# lcd_panel_adapter.net
KiCad netlist of a schematic drawn in EAGLE
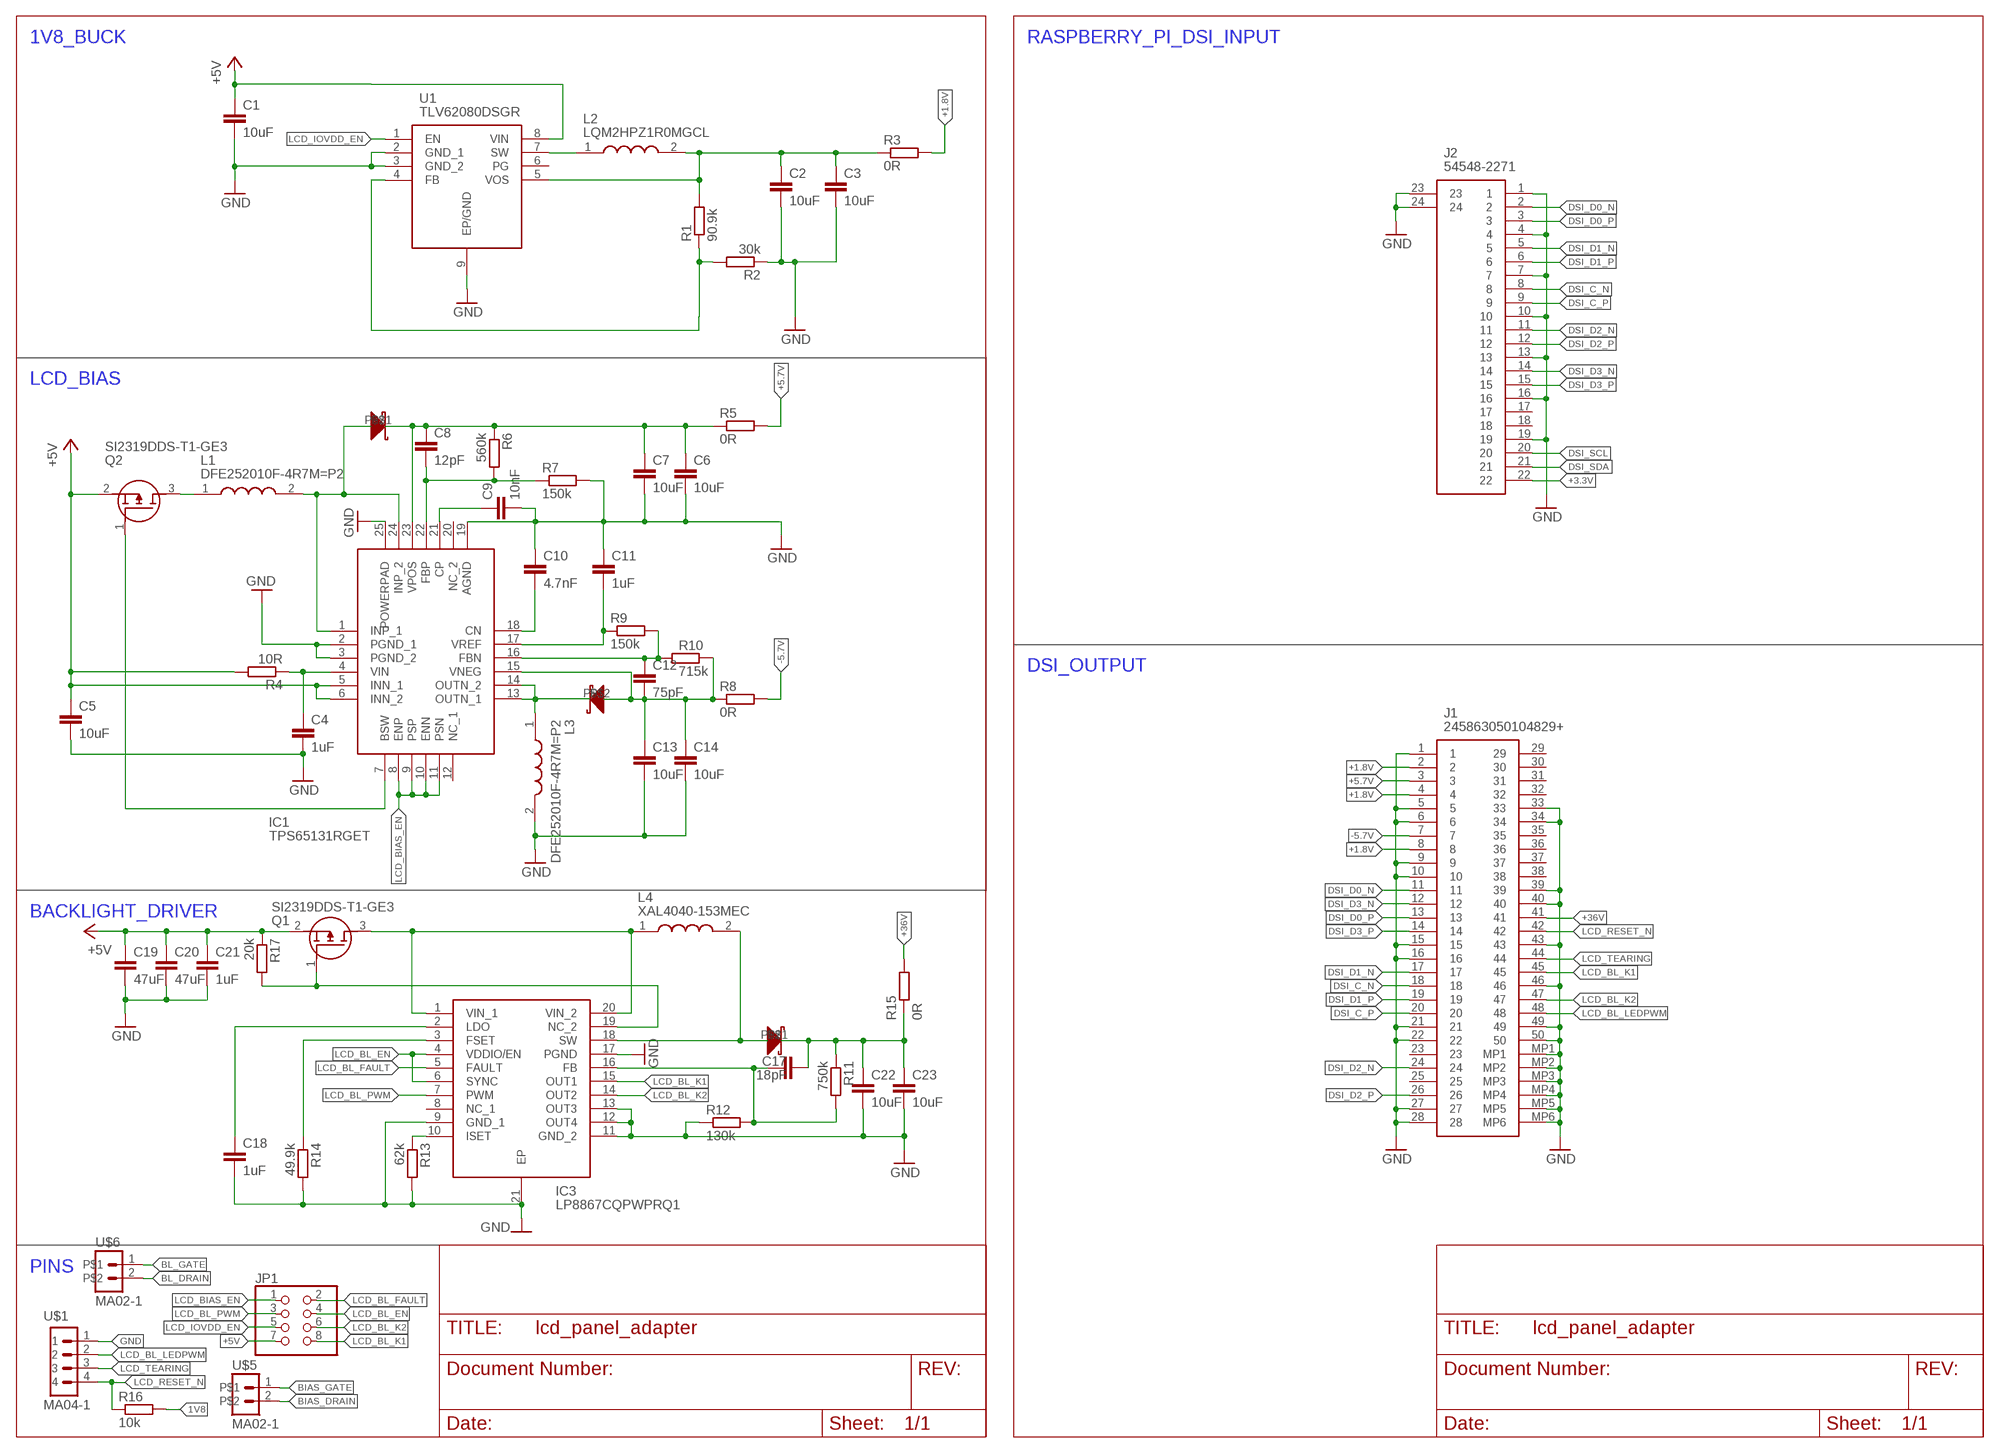
[diagram p0: schematic, sheet 1]

(export (version "E")
  (design (tool "Eeschema 10.0.6"))
  (components
    (comp (ref "C1")
      (value "10uF")
      (footprint "eagle-import:C0603")
      (libsource (lib "eagle-import") (part "C-EUC0603"))
    )
    (comp (ref "C2")
      (value "10uF")
      (footprint "eagle-import:C0603")
      (libsource (lib "eagle-import") (part "C-EUC0603"))
    )
    (comp (ref "C3")
      (value "10uF")
      (footprint "eagle-import:C0603")
      (libsource (lib "eagle-import") (part "C-EUC0603"))
    )
    (comp (ref "C4")
      (value "1uF")
      (footprint "eagle-import:C0603")
      (libsource (lib "eagle-import") (part "C-EUC0603"))
    )
    (comp (ref "C5")
      (value "10uF")
      (footprint "eagle-import:C0603")
      (libsource (lib "eagle-import") (part "C-EUC0603"))
    )
    (comp (ref "C6")
      (value "10uF")
      (footprint "eagle-import:C0603")
      (libsource (lib "eagle-import") (part "C-EUC0603"))
    )
    (comp (ref "C7")
      (value "10uF")
      (footprint "eagle-import:C0603")
      (libsource (lib "eagle-import") (part "C-EUC0603"))
    )
    (comp (ref "C8")
      (value "12pF")
      (footprint "eagle-import:C0603")
      (libsource (lib "eagle-import") (part "C-EUC0603"))
    )
    (comp (ref "C9")
      (value "10nF")
      (footprint "eagle-import:C0603")
      (libsource (lib "eagle-import") (part "C-EUC0603"))
    )
    (comp (ref "C10")
      (value "4.7nF")
      (footprint "eagle-import:C0603")
      (libsource (lib "eagle-import") (part "C-EUC0603"))
    )
    (comp (ref "C11")
      (value "1uF")
      (footprint "eagle-import:C0603")
      (libsource (lib "eagle-import") (part "C-EUC0603"))
    )
    (comp (ref "C12")
      (value "75pF")
      (footprint "eagle-import:C0603")
      (libsource (lib "eagle-import") (part "C-EUC0603"))
    )
    (comp (ref "C13")
      (value "10uF")
      (footprint "eagle-import:C0603")
      (libsource (lib "eagle-import") (part "C-EUC0603"))
    )
    (comp (ref "C14")
      (value "10uF")
      (footprint "eagle-import:C0603")
      (libsource (lib "eagle-import") (part "C-EUC0603"))
    )
    (comp (ref "C17")
      (value "18pF")
      (footprint "eagle-import:C0603")
      (libsource (lib "eagle-import") (part "C-EUC0603"))
    )
    (comp (ref "C18")
      (value "1uF")
      (footprint "eagle-import:C0603")
      (libsource (lib "eagle-import") (part "C-EUC0603"))
    )
    (comp (ref "C19")
      (value "47uF")
      (footprint "eagle-import:C0603")
      (libsource (lib "eagle-import") (part "C-EUC0603"))
    )
    (comp (ref "C20")
      (value "47uF")
      (footprint "eagle-import:C0603")
      (libsource (lib "eagle-import") (part "C-EUC0603"))
    )
    (comp (ref "C21")
      (value "1uF")
      (footprint "eagle-import:C0603")
      (libsource (lib "eagle-import") (part "C-EUC0603"))
    )
    (comp (ref "C22")
      (value "10uF")
      (footprint "eagle-import:C1206")
      (libsource (lib "eagle-import") (part "C-EUC1206"))
    )
    (comp (ref "C23")
      (value "10uF")
      (footprint "eagle-import:C1206")
      (libsource (lib "eagle-import") (part "C-EUC1206"))
    )
    (comp (ref "IC1")
      (value "TPS65131RGET")
      (footprint "eagle-import:QFN50P400X400X100-25N")
      (fields (field (name "MOUSER_PART_NUMBER") "595-TPS65131RGET"))
      (libsource (lib "eagle-import") (part "TPS65131RGET"))
    )
    (comp (ref "IC3")
      (value "LP8867CQPWPRQ1")
      (footprint "eagle-import:SOP65P640X120-21N")
      (fields
        (field (name "MANUFACTURER_PART_NUMBER") "TPS61194PWPR")
        (field (name "MOUSER_PART_NUMBER") "595-TPS61194PWPR")
      )
      (libsource (lib "eagle-import") (part "TPS61194PWPR"))
    )
    (comp (ref "J1")
      (value "245863050104829+")
      (footprint "eagle-import:245863050104829")
      (fields (field (name "MOUSER_PART_NUMBER") "346-245863050104829+"))
      (libsource (lib "eagle-import") (part "245863050104829+"))
    )
    (comp (ref "J2")
      (value "54548-2271")
      (footprint "eagle-import:545482271")
      (fields (field (name "MOUSER_PART_NUMBER") "538-54548-2271"))
      (libsource (lib "eagle-import") (part "54548-2271"))
    )
    (comp (ref "JP1")
      (value "PINHD-2X4")
      (footprint "eagle-import:2X04")
      (libsource (lib "eagle-import") (part "PINHD-2X4"))
    )
    (comp (ref "L1")
      (value "DFE252010F-4R7M=P2")
      (footprint "eagle-import:1269ASH100NP2")
      (fields (field (name "MOUSER_PART_NUMBER") "81-DFE252010F-4R7MP2"))
      (libsource (lib "eagle-import") (part "DFE252010F-4R7M=P2"))
    )
    (comp (ref "L2")
      (value "LQM2HPZ1R0MGCL")
      (footprint "eagle-import:LQM2HPN1R0MG0L")
      (libsource (lib "eagle-import") (part "LQM2HPZ1R0MGCL"))
    )
    (comp (ref "L3")
      (value "DFE252010F-4R7M=P2")
      (footprint "eagle-import:1269ASH100NP2")
      (fields (field (name "MOUSER_PART_NUMBER") "81-DFE252010F-4R7MP2"))
      (libsource (lib "eagle-import") (part "DFE252010F-4R7M=P2"))
    )
    (comp (ref "L4")
      (value "XAL4040-153MEC")
      (footprint "eagle-import:XAL4040153MEC")
      (fields (field (name "MOUSER_PART_NUMBER") "994-XAL4040-153MEC"))
      (libsource (lib "eagle-import") (part "XAL4040-153MEC"))
    )
    (comp (ref "Q1")
      (value "SI2319DDS-T1-GE3")
      (footprint "eagle-import:SOT96P240X120-3N")
      (fields (field (name "MOUSER_PART_NUMBER") "78-SI2319DDS-T1-GE3"))
      (libsource (lib "eagle-import") (part "SI2319DDS-T1-GE3"))
    )
    (comp (ref "Q2")
      (value "SI2319DDS-T1-GE3")
      (footprint "eagle-import:SOT96P240X120-3N")
      (fields (field (name "MOUSER_PART_NUMBER") "78-SI2319DDS-T1-GE3"))
      (libsource (lib "eagle-import") (part "SI2319DDS-T1-GE3"))
    )
    (comp (ref "R1")
      (value "90.9k")
      (footprint "eagle-import:R0603")
      (libsource (lib "eagle-import") (part "R-EU_R0603"))
    )
    (comp (ref "R2")
      (value "30k")
      (footprint "eagle-import:R0603")
      (libsource (lib "eagle-import") (part "R-EU_R0603"))
    )
    (comp (ref "R3")
      (value "0R")
      (footprint "eagle-import:R0603")
      (libsource (lib "eagle-import") (part "R-EU_R0603"))
    )
    (comp (ref "R4")
      (value "10R")
      (footprint "eagle-import:R0603")
      (libsource (lib "eagle-import") (part "R-EU_R0603"))
    )
    (comp (ref "R5")
      (value "0R")
      (footprint "eagle-import:R0603")
      (libsource (lib "eagle-import") (part "R-EU_R0603"))
    )
    (comp (ref "R6")
      (value "560k")
      (footprint "eagle-import:R0603")
      (libsource (lib "eagle-import") (part "R-EU_R0603"))
    )
    (comp (ref "R7")
      (value "150k")
      (footprint "eagle-import:R0603")
      (libsource (lib "eagle-import") (part "R-EU_R0603"))
    )
    (comp (ref "R8")
      (value "0R")
      (footprint "eagle-import:R0603")
      (libsource (lib "eagle-import") (part "R-EU_R0603"))
    )
    (comp (ref "R9")
      (value "150k")
      (footprint "eagle-import:R0603")
      (libsource (lib "eagle-import") (part "R-EU_R0603"))
    )
    (comp (ref "R10")
      (value "715k")
      (footprint "eagle-import:R0603")
      (libsource (lib "eagle-import") (part "R-EU_R0603"))
    )
    (comp (ref "R11")
      (value "750k")
      (footprint "eagle-import:R0603")
      (libsource (lib "eagle-import") (part "R-EU_R0603"))
    )
    (comp (ref "R12")
      (value "130k")
      (footprint "eagle-import:R0603")
      (libsource (lib "eagle-import") (part "R-EU_R0603"))
    )
    (comp (ref "R13")
      (value "62k")
      (footprint "eagle-import:R0603")
      (libsource (lib "eagle-import") (part "R-EU_R0603"))
    )
    (comp (ref "R14")
      (value "49.9k")
      (footprint "eagle-import:R0603")
      (libsource (lib "eagle-import") (part "R-EU_R0603"))
    )
    (comp (ref "R15")
      (value "0R")
      (footprint "eagle-import:R0603")
      (libsource (lib "eagle-import") (part "R-EU_R0603"))
    )
    (comp (ref "R16")
      (value "10k")
      (footprint "eagle-import:R0603")
      (libsource (lib "eagle-import") (part "R-EU_R0603"))
    )
    (comp (ref "R17")
      (value "20k")
      (footprint "eagle-import:R0603")
      (libsource (lib "eagle-import") (part "R-EU_R0603"))
    )
    (comp (ref "U$1")
      (value "MA04-1")
      (footprint "eagle-import:MA04-1")
      (libsource (lib "eagle-import") (part "MA04-1"))
    )
    (comp (ref "U$2")
      (value "CUS10S40")
      (footprint "eagle-import:CUS10S40")
      (libsource (lib "eagle-import") (part "CUS10S40"))
    )
    (comp (ref "U$3")
      (value "CUS10S40")
      (footprint "eagle-import:CUS10S40")
      (libsource (lib "eagle-import") (part "CUS10S40"))
    )
    (comp (ref "U$4")
      (value "CUS10S40")
      (footprint "eagle-import:CUS10S40")
      (libsource (lib "eagle-import") (part "CUS10S40"))
    )
    (comp (ref "U$5")
      (value "MA02-1")
      (footprint "eagle-import:MA02-1")
      (libsource (lib "eagle-import") (part "MA02-1"))
    )
    (comp (ref "U$6")
      (value "MA02-1")
      (footprint "eagle-import:MA02-1")
      (libsource (lib "eagle-import") (part "MA02-1"))
    )
    (comp (ref "U1")
      (value "TLV62080DSGR")
      (footprint "eagle-import:SON50P200X200X80-9N")
      (fields (field (name "MOUSER_PART_NUMBER") "595-TLV62080DSGR"))
      (libsource (lib "eagle-import") (part "TLV62080DSGR"))
    )
  )
  (nets
    (net (code "1") (name "+1.8V") (class "Default")
      (node (ref "J1") (pin "2") (pinfunction "2_2") (pintype "bidirectional"))
      (node (ref "J1") (pin "4") (pinfunction "4_4") (pintype "bidirectional"))
      (node (ref "J1") (pin "8") (pinfunction "8_8") (pintype "bidirectional"))
      (node (ref "R3") (pin "2") (pinfunction "2_2") (pintype "passive"))
    )
    (net (code "2") (name "+3.3V") (class "Default")
      (node (ref "J2") (pin "22") (pinfunction "22_22") (pintype "bidirectional"))
    )
    (net (code "3") (name "+5.7V") (class "Default")
      (node (ref "J1") (pin "3") (pinfunction "3_3") (pintype "bidirectional"))
      (node (ref "R5") (pin "2") (pinfunction "2_2") (pintype "passive"))
    )
    (net (code "4") (name "+5V") (class "Default")
      (node (ref "C1") (pin "1") (pinfunction "1_1") (pintype "passive"))
      (node (ref "C19") (pin "1") (pinfunction "1_1") (pintype "passive"))
      (node (ref "C20") (pin "1") (pinfunction "1_1") (pintype "passive"))
      (node (ref "C21") (pin "1") (pinfunction "1_1") (pintype "passive"))
      (node (ref "C5") (pin "1") (pinfunction "1_1") (pintype "passive"))
      (node (ref "IC1") (pin "5") (pinfunction "INN_1_5") (pintype "bidirectional"))
      (node (ref "IC1") (pin "6") (pinfunction "INN_2_6") (pintype "bidirectional"))
      (node (ref "JP1") (pin "7") (pinfunction "7_7") (pintype "passive"))
      (node (ref "Q1") (pin "2") (pinfunction "S_2") (pintype "bidirectional"))
      (node (ref "Q2") (pin "2") (pinfunction "S_2") (pintype "bidirectional"))
      (node (ref "R17") (pin "1") (pinfunction "1_1") (pintype "passive"))
      (node (ref "R4") (pin "2") (pinfunction "2_2") (pintype "passive"))
      (node (ref "U1") (pin "8") (pinfunction "VIN_8") (pintype "bidirectional"))
    )
    (net (code "5") (name "+36V") (class "Default")
      (node (ref "J1") (pin "41") (pinfunction "41_41") (pintype "bidirectional"))
      (node (ref "R15") (pin "2") (pinfunction "2_2") (pintype "passive"))
    )
    (net (code "6") (name "-5.7V") (class "Default")
      (node (ref "J1") (pin "7") (pinfunction "7_7") (pintype "bidirectional"))
      (node (ref "R8") (pin "2") (pinfunction "2_2") (pintype "passive"))
    )
    (net (code "7") (name "1V8") (class "Default")
      (node (ref "C2") (pin "1") (pinfunction "1_1") (pintype "passive"))
      (node (ref "C3") (pin "1") (pinfunction "1_1") (pintype "passive"))
      (node (ref "L2") (pin "2") (pinfunction "2_2") (pintype "bidirectional"))
      (node (ref "R1") (pin "2") (pinfunction "2_2") (pintype "passive"))
      (node (ref "R16") (pin "2") (pinfunction "2_2") (pintype "passive"))
      (node (ref "R3") (pin "1") (pinfunction "1_1") (pintype "passive"))
      (node (ref "U1") (pin "5") (pinfunction "VOS_5") (pintype "bidirectional"))
    )
    (net (code "8") (name "BIAS_DRAIN") (class "Default")
      (node (ref "L1") (pin "1") (pinfunction "1_1") (pintype "bidirectional"))
      (node (ref "Q2") (pin "3") (pinfunction "D_3") (pintype "bidirectional"))
      (node (ref "U$5") (pin "2") (pinfunction "P$2_2") (pintype "bidirectional"))
    )
    (net (code "9") (name "BIAS_GATE") (class "Default")
      (node (ref "IC1") (pin "7") (pinfunction "BSW_7") (pintype "bidirectional"))
      (node (ref "Q2") (pin "1") (pinfunction "G_1") (pintype "bidirectional"))
      (node (ref "U$5") (pin "1") (pinfunction "P$1_1") (pintype "bidirectional"))
    )
    (net (code "10") (name "BL_DRAIN") (class "Default")
      (node (ref "IC3") (pin "1") (pinfunction "VIN_1_1") (pintype "bidirectional"))
      (node (ref "IC3") (pin "20") (pinfunction "VIN_2_20") (pintype "bidirectional"))
      (node (ref "L4") (pin "1") (pinfunction "1_1") (pintype "bidirectional"))
      (node (ref "Q1") (pin "3") (pinfunction "D_3") (pintype "bidirectional"))
      (node (ref "U$6") (pin "2") (pinfunction "P$2_2") (pintype "bidirectional"))
    )
    (net (code "11") (name "BL_GATE") (class "Default")
      (node (ref "IC3") (pin "19") (pinfunction "NC_2_19") (pintype "bidirectional"))
      (node (ref "Q1") (pin "1") (pinfunction "G_1") (pintype "bidirectional"))
      (node (ref "R17") (pin "2") (pinfunction "2_2") (pintype "passive"))
      (node (ref "U$6") (pin "1") (pinfunction "P$1_1") (pintype "bidirectional"))
    )
    (net (code "12") (name "DSI_C_N") (class "Default")
      (node (ref "J1") (pin "18") (pinfunction "18_18") (pintype "bidirectional"))
      (node (ref "J2") (pin "8") (pinfunction "8_8") (pintype "bidirectional"))
    )
    (net (code "13") (name "DSI_C_P") (class "Default")
      (node (ref "J1") (pin "20") (pinfunction "20_20") (pintype "bidirectional"))
      (node (ref "J2") (pin "9") (pinfunction "9_9") (pintype "bidirectional"))
    )
    (net (code "14") (name "DSI_D0_N") (class "Default")
      (node (ref "J1") (pin "11") (pinfunction "11_11") (pintype "bidirectional"))
      (node (ref "J2") (pin "2") (pinfunction "2_2") (pintype "bidirectional"))
    )
    (net (code "15") (name "DSI_D0_P") (class "Default")
      (node (ref "J1") (pin "13") (pinfunction "13_13") (pintype "bidirectional"))
      (node (ref "J2") (pin "3") (pinfunction "3_3") (pintype "bidirectional"))
    )
    (net (code "16") (name "DSI_D1_N") (class "Default")
      (node (ref "J1") (pin "17") (pinfunction "17_17") (pintype "bidirectional"))
      (node (ref "J2") (pin "5") (pinfunction "5_5") (pintype "bidirectional"))
    )
    (net (code "17") (name "DSI_D1_P") (class "Default")
      (node (ref "J1") (pin "19") (pinfunction "19_19") (pintype "bidirectional"))
      (node (ref "J2") (pin "6") (pinfunction "6_6") (pintype "bidirectional"))
    )
    (net (code "18") (name "DSI_D2_N") (class "Default")
      (node (ref "J1") (pin "24") (pinfunction "24_24") (pintype "bidirectional"))
      (node (ref "J2") (pin "11") (pinfunction "11_11") (pintype "bidirectional"))
    )
    (net (code "19") (name "DSI_D2_P") (class "Default")
      (node (ref "J1") (pin "26") (pinfunction "26_26") (pintype "bidirectional"))
      (node (ref "J2") (pin "12") (pinfunction "12_12") (pintype "bidirectional"))
    )
    (net (code "20") (name "DSI_D3_N") (class "Default")
      (node (ref "J1") (pin "12") (pinfunction "12_12") (pintype "bidirectional"))
      (node (ref "J2") (pin "14") (pinfunction "14_14") (pintype "bidirectional"))
    )
    (net (code "21") (name "DSI_D3_P") (class "Default")
      (node (ref "J1") (pin "14") (pinfunction "14_14") (pintype "bidirectional"))
      (node (ref "J2") (pin "15") (pinfunction "15_15") (pintype "bidirectional"))
    )
    (net (code "22") (name "DSI_SCL") (class "Default")
      (node (ref "J2") (pin "20") (pinfunction "20_20") (pintype "bidirectional"))
    )
    (net (code "23") (name "DSI_SDA") (class "Default")
      (node (ref "J2") (pin "21") (pinfunction "21_21") (pintype "bidirectional"))
    )
    (net (code "24") (name "GND") (class "Default")
      (node (ref "C1") (pin "2") (pinfunction "2_2") (pintype "passive"))
      (node (ref "C10") (pin "1") (pinfunction "1_1") (pintype "passive"))
      (node (ref "C11") (pin "1") (pinfunction "1_1") (pintype "passive"))
      (node (ref "C13") (pin "2") (pinfunction "2_2") (pintype "passive"))
      (node (ref "C14") (pin "2") (pinfunction "2_2") (pintype "passive"))
      (node (ref "C18") (pin "2") (pinfunction "2_2") (pintype "passive"))
      (node (ref "C19") (pin "2") (pinfunction "2_2") (pintype "passive"))
      (node (ref "C2") (pin "2") (pinfunction "2_2") (pintype "passive"))
      (node (ref "C20") (pin "2") (pinfunction "2_2") (pintype "passive"))
      (node (ref "C21") (pin "2") (pinfunction "2_2") (pintype "passive"))
      (node (ref "C22") (pin "2") (pinfunction "2_2") (pintype "passive"))
      (node (ref "C23") (pin "2") (pinfunction "2_2") (pintype "passive"))
      (node (ref "C3") (pin "2") (pinfunction "2_2") (pintype "passive"))
      (node (ref "C4") (pin "2") (pinfunction "2_2") (pintype "passive"))
      (node (ref "C5") (pin "2") (pinfunction "2_2") (pintype "passive"))
      (node (ref "C6") (pin "2") (pinfunction "2_2") (pintype "passive"))
      (node (ref "C7") (pin "2") (pinfunction "2_2") (pintype "passive"))
      (node (ref "C9") (pin "2") (pinfunction "2_2") (pintype "passive"))
      (node (ref "IC1") (pin "19") (pinfunction "AGND_19") (pintype "bidirectional"))
      (node (ref "IC1") (pin "2") (pinfunction "PGND_1_2") (pintype "bidirectional"))
      (node (ref "IC1") (pin "25") (pinfunction "POWERPAD_25") (pintype "bidirectional"))
      (node (ref "IC1") (pin "3") (pinfunction "PGND_2_3") (pintype "bidirectional"))
      (node (ref "IC3") (pin "11") (pinfunction "GND_2_11") (pintype "bidirectional"))
      (node (ref "IC3") (pin "12") (pinfunction "OUT4_12") (pintype "bidirectional"))
      (node (ref "IC3") (pin "13") (pinfunction "OUT3_13") (pintype "bidirectional"))
      (node (ref "IC3") (pin "17") (pinfunction "PGND_17") (pintype "bidirectional"))
      (node (ref "IC3") (pin "21") (pinfunction "EP_21") (pintype "bidirectional"))
      (node (ref "IC3") (pin "9") (pinfunction "GND_1_9") (pintype "bidirectional"))
      (node (ref "J1") (pin "1") (pinfunction "1_1") (pintype "bidirectional"))
      (node (ref "J1") (pin "10") (pinfunction "10_10") (pintype "bidirectional"))
      (node (ref "J1") (pin "15") (pinfunction "15_15") (pintype "bidirectional"))
      (node (ref "J1") (pin "16") (pinfunction "16_16") (pintype "bidirectional"))
      (node (ref "J1") (pin "21") (pinfunction "21_21") (pintype "bidirectional"))
      (node (ref "J1") (pin "22") (pinfunction "22_22") (pintype "bidirectional"))
      (node (ref "J1") (pin "27") (pinfunction "27_27") (pintype "bidirectional"))
      (node (ref "J1") (pin "28") (pinfunction "28_28") (pintype "bidirectional"))
      (node (ref "J1") (pin "33") (pinfunction "33_33") (pintype "bidirectional"))
      (node (ref "J1") (pin "34") (pinfunction "34_34") (pintype "bidirectional"))
      (node (ref "J1") (pin "39") (pinfunction "39_39") (pintype "bidirectional"))
      (node (ref "J1") (pin "40") (pinfunction "40_40") (pintype "bidirectional"))
      (node (ref "J1") (pin "43") (pinfunction "43_43") (pintype "bidirectional"))
      (node (ref "J1") (pin "46") (pinfunction "46_46") (pintype "bidirectional"))
      (node (ref "J1") (pin "49") (pinfunction "49_49") (pintype "bidirectional"))
      (node (ref "J1") (pin "5") (pinfunction "5_5") (pintype "bidirectional"))
      (node (ref "J1") (pin "50") (pinfunction "50_50") (pintype "bidirectional"))
      (node (ref "J1") (pin "6") (pinfunction "6_6") (pintype "bidirectional"))
      (node (ref "J1") (pin "9") (pinfunction "9_9") (pintype "bidirectional"))
      (node (ref "J1") (pin "MP1") (pinfunction "MP1_MP1") (pintype "bidirectional"))
      (node (ref "J1") (pin "MP2") (pinfunction "MP2_MP2") (pintype "bidirectional"))
      (node (ref "J1") (pin "MP3") (pinfunction "MP3_MP3") (pintype "bidirectional"))
      (node (ref "J1") (pin "MP4") (pinfunction "MP4_MP4") (pintype "bidirectional"))
      (node (ref "J1") (pin "MP5") (pinfunction "MP5_MP5") (pintype "bidirectional"))
      (node (ref "J1") (pin "MP6") (pinfunction "MP6_MP6") (pintype "bidirectional"))
      (node (ref "J2") (pin "1") (pinfunction "1_1") (pintype "bidirectional"))
      (node (ref "J2") (pin "10") (pinfunction "10_10") (pintype "bidirectional"))
      (node (ref "J2") (pin "13") (pinfunction "13_13") (pintype "bidirectional"))
      (node (ref "J2") (pin "16") (pinfunction "16_16") (pintype "bidirectional"))
      (node (ref "J2") (pin "19") (pinfunction "19_19") (pintype "bidirectional"))
      (node (ref "J2") (pin "23") (pinfunction "23_23") (pintype "bidirectional"))
      (node (ref "J2") (pin "24") (pinfunction "24_24") (pintype "bidirectional"))
      (node (ref "J2") (pin "4") (pinfunction "4_4") (pintype "bidirectional"))
      (node (ref "J2") (pin "7") (pinfunction "7_7") (pintype "bidirectional"))
      (node (ref "L3") (pin "2") (pinfunction "2_2") (pintype "bidirectional"))
      (node (ref "R12") (pin "1") (pinfunction "1_1") (pintype "passive"))
      (node (ref "R13") (pin "2") (pinfunction "2_2") (pintype "passive"))
      (node (ref "R14") (pin "2") (pinfunction "2_2") (pintype "passive"))
      (node (ref "R2") (pin "1") (pinfunction "1_1") (pintype "passive"))
      (node (ref "R7") (pin "2") (pinfunction "2_2") (pintype "passive"))
      (node (ref "U$1") (pin "1") (pinfunction "1_1") (pintype "bidirectional"))
      (node (ref "U1") (pin "2") (pinfunction "GND_1_2") (pintype "bidirectional"))
      (node (ref "U1") (pin "3") (pinfunction "GND_2_3") (pintype "bidirectional"))
      (node (ref "U1") (pin "9") (pinfunction "EP/GND_9") (pintype "bidirectional"))
    )
    (net (code "25") (name "LCD_BIAS_EN") (class "Default")
      (node (ref "IC1") (pin "10") (pinfunction "ENN_10") (pintype "bidirectional"))
      (node (ref "IC1") (pin "11") (pinfunction "PSN_11") (pintype "bidirectional"))
      (node (ref "IC1") (pin "8") (pinfunction "ENP_8") (pintype "bidirectional"))
      (node (ref "IC1") (pin "9") (pinfunction "PSP_9") (pintype "bidirectional"))
      (node (ref "JP1") (pin "1") (pinfunction "1_1") (pintype "passive"))
    )
    (net (code "26") (name "LCD_BL_EN") (class "Default")
      (node (ref "IC3") (pin "4") (pinfunction "VDDIO/EN_4") (pintype "bidirectional"))
      (node (ref "IC3") (pin "6") (pinfunction "SYNC_6") (pintype "bidirectional"))
      (node (ref "JP1") (pin "4") (pinfunction "4_4") (pintype "passive"))
    )
    (net (code "27") (name "LCD_BL_FAULT") (class "Default")
      (node (ref "IC3") (pin "5") (pinfunction "FAULT_5") (pintype "bidirectional"))
      (node (ref "JP1") (pin "2") (pinfunction "2_2") (pintype "passive"))
    )
    (net (code "28") (name "LCD_BL_K1") (class "Default")
      (node (ref "IC3") (pin "15") (pinfunction "OUT1_15") (pintype "bidirectional"))
      (node (ref "J1") (pin "45") (pinfunction "45_45") (pintype "bidirectional"))
      (node (ref "JP1") (pin "8") (pinfunction "8_8") (pintype "passive"))
    )
    (net (code "29") (name "LCD_BL_K2") (class "Default")
      (node (ref "IC3") (pin "14") (pinfunction "OUT2_14") (pintype "bidirectional"))
      (node (ref "J1") (pin "47") (pinfunction "47_47") (pintype "bidirectional"))
      (node (ref "JP1") (pin "6") (pinfunction "6_6") (pintype "passive"))
    )
    (net (code "30") (name "LCD_BL_LEDPWM") (class "Default")
      (node (ref "J1") (pin "48") (pinfunction "48_48") (pintype "bidirectional"))
      (node (ref "U$1") (pin "2") (pinfunction "2_2") (pintype "bidirectional"))
    )
    (net (code "31") (name "LCD_BL_PWM") (class "Default")
      (node (ref "IC3") (pin "7") (pinfunction "PWM_7") (pintype "bidirectional"))
      (node (ref "JP1") (pin "3") (pinfunction "3_3") (pintype "passive"))
    )
    (net (code "32") (name "LCD_IOVDD_EN") (class "Default")
      (node (ref "JP1") (pin "5") (pinfunction "5_5") (pintype "passive"))
      (node (ref "U1") (pin "1") (pinfunction "EN_1") (pintype "bidirectional"))
    )
    (net (code "33") (name "LCD_RESET_N") (class "Default")
      (node (ref "J1") (pin "42") (pinfunction "42_42") (pintype "bidirectional"))
      (node (ref "R16") (pin "1") (pinfunction "1_1") (pintype "passive"))
      (node (ref "U$1") (pin "4") (pinfunction "4_4") (pintype "bidirectional"))
    )
    (net (code "34") (name "LCD_TEARING") (class "Default")
      (node (ref "J1") (pin "44") (pinfunction "44_44") (pintype "bidirectional"))
      (node (ref "U$1") (pin "3") (pinfunction "3_3") (pintype "bidirectional"))
    )
    (net (code "35") (name "Net-(C17-Pad2)") (class "Default")
      (node (ref "C17") (pin "2") (pinfunction "2_2") (pintype "passive"))
      (node (ref "C22") (pin "1") (pinfunction "1_1") (pintype "passive"))
      (node (ref "C23") (pin "1") (pinfunction "1_1") (pintype "passive"))
      (node (ref "R11") (pin "1") (pinfunction "1_1") (pintype "passive"))
      (node (ref "R15") (pin "1") (pinfunction "1_1") (pintype "passive"))
      (node (ref "U$4") (pin "P$2") (pinfunction "P$2_P$2") (pintype "bidirectional"))
    )
    (net (code "36") (name "Net-(IC1-CN)") (class "Default")
      (node (ref "C10") (pin "2") (pinfunction "2_2") (pintype "passive"))
      (node (ref "IC1") (pin "18") (pinfunction "CN_18") (pintype "bidirectional"))
    )
    (net (code "37") (name "Net-(IC1-CP)") (class "Default")
      (node (ref "C9") (pin "1") (pinfunction "1_1") (pintype "passive"))
      (node (ref "IC1") (pin "21") (pinfunction "CP_21") (pintype "bidirectional"))
    )
    (net (code "38") (name "Net-(IC1-FBN)") (class "Default")
      (node (ref "C12") (pin "1") (pinfunction "1_1") (pintype "passive"))
      (node (ref "IC1") (pin "16") (pinfunction "FBN_16") (pintype "bidirectional"))
      (node (ref "R10") (pin "1") (pinfunction "1_1") (pintype "passive"))
      (node (ref "R9") (pin "2") (pinfunction "2_2") (pintype "passive"))
    )
    (net (code "39") (name "Net-(IC1-FBP)") (class "Default")
      (node (ref "C8") (pin "2") (pinfunction "2_2") (pintype "passive"))
      (node (ref "IC1") (pin "22") (pinfunction "FBP_22") (pintype "bidirectional"))
      (node (ref "R6") (pin "2") (pinfunction "2_2") (pintype "passive"))
      (node (ref "R7") (pin "1") (pinfunction "1_1") (pintype "passive"))
    )
    (net (code "40") (name "Net-(IC1-INP_1)") (class "Default")
      (node (ref "IC1") (pin "1") (pinfunction "INP_1_1") (pintype "bidirectional"))
      (node (ref "IC1") (pin "24") (pinfunction "INP_2_24") (pintype "bidirectional"))
      (node (ref "L1") (pin "2") (pinfunction "2_2") (pintype "bidirectional"))
      (node (ref "U$2") (pin "P$1") (pinfunction "P$1_P$1") (pintype "bidirectional"))
    )
    (net (code "41") (name "Net-(IC1-OUTN_1)") (class "Default")
      (node (ref "IC1") (pin "13") (pinfunction "OUTN_1_13") (pintype "bidirectional"))
      (node (ref "IC1") (pin "14") (pinfunction "OUTN_2_14") (pintype "bidirectional"))
      (node (ref "L3") (pin "1") (pinfunction "1_1") (pintype "bidirectional"))
      (node (ref "U$3") (pin "P$2") (pinfunction "P$2_P$2") (pintype "bidirectional"))
    )
    (net (code "42") (name "Net-(IC1-VIN)") (class "Default")
      (node (ref "C4") (pin "1") (pinfunction "1_1") (pintype "passive"))
      (node (ref "IC1") (pin "4") (pinfunction "VIN_4") (pintype "bidirectional"))
      (node (ref "R4") (pin "1") (pinfunction "1_1") (pintype "passive"))
    )
    (net (code "43") (name "Net-(IC1-VNEG)") (class "Default")
      (node (ref "C12") (pin "2") (pinfunction "2_2") (pintype "passive"))
      (node (ref "C13") (pin "1") (pinfunction "1_1") (pintype "passive"))
      (node (ref "C14") (pin "1") (pinfunction "1_1") (pintype "passive"))
      (node (ref "IC1") (pin "15") (pinfunction "VNEG_15") (pintype "bidirectional"))
      (node (ref "R10") (pin "2") (pinfunction "2_2") (pintype "passive"))
      (node (ref "R8") (pin "1") (pinfunction "1_1") (pintype "passive"))
      (node (ref "U$3") (pin "P$1") (pinfunction "P$1_P$1") (pintype "bidirectional"))
    )
    (net (code "44") (name "Net-(IC1-VPOS)") (class "Default")
      (node (ref "C6") (pin "1") (pinfunction "1_1") (pintype "passive"))
      (node (ref "C7") (pin "1") (pinfunction "1_1") (pintype "passive"))
      (node (ref "C8") (pin "1") (pinfunction "1_1") (pintype "passive"))
      (node (ref "IC1") (pin "23") (pinfunction "VPOS_23") (pintype "bidirectional"))
      (node (ref "R5") (pin "1") (pinfunction "1_1") (pintype "passive"))
      (node (ref "R6") (pin "1") (pinfunction "1_1") (pintype "passive"))
      (node (ref "U$2") (pin "P$2") (pinfunction "P$2_P$2") (pintype "bidirectional"))
    )
    (net (code "45") (name "Net-(IC1-VREF)") (class "Default")
      (node (ref "C11") (pin "2") (pinfunction "2_2") (pintype "passive"))
      (node (ref "IC1") (pin "17") (pinfunction "VREF_17") (pintype "bidirectional"))
      (node (ref "R9") (pin "1") (pinfunction "1_1") (pintype "passive"))
    )
    (net (code "46") (name "Net-(IC3-FB)") (class "Default")
      (node (ref "C17") (pin "1") (pinfunction "1_1") (pintype "passive"))
      (node (ref "IC3") (pin "16") (pinfunction "FB_16") (pintype "bidirectional"))
      (node (ref "R11") (pin "2") (pinfunction "2_2") (pintype "passive"))
      (node (ref "R12") (pin "2") (pinfunction "2_2") (pintype "passive"))
    )
    (net (code "47") (name "Net-(IC3-FSET)") (class "Default")
      (node (ref "IC3") (pin "3") (pinfunction "FSET_3") (pintype "bidirectional"))
      (node (ref "R14") (pin "1") (pinfunction "1_1") (pintype "passive"))
    )
    (net (code "48") (name "Net-(IC3-ISET)") (class "Default")
      (node (ref "IC3") (pin "10") (pinfunction "ISET_10") (pintype "bidirectional"))
      (node (ref "R13") (pin "1") (pinfunction "1_1") (pintype "passive"))
    )
    (net (code "49") (name "Net-(IC3-LDO)") (class "Default")
      (node (ref "C18") (pin "1") (pinfunction "1_1") (pintype "passive"))
      (node (ref "IC3") (pin "2") (pinfunction "LDO_2") (pintype "bidirectional"))
    )
    (net (code "50") (name "Net-(IC3-SW)") (class "Default")
      (node (ref "IC3") (pin "18") (pinfunction "SW_18") (pintype "bidirectional"))
      (node (ref "L4") (pin "2") (pinfunction "2_2") (pintype "bidirectional"))
      (node (ref "U$4") (pin "P$1") (pinfunction "P$1_P$1") (pintype "bidirectional"))
    )
    (net (code "51") (name "Net-(U1-FB)") (class "Default")
      (node (ref "R1") (pin "1") (pinfunction "1_1") (pintype "passive"))
      (node (ref "R2") (pin "2") (pinfunction "2_2") (pintype "passive"))
      (node (ref "U1") (pin "4") (pinfunction "FB_4") (pintype "bidirectional"))
    )
    (net (code "52") (name "Net-(U1-SW)") (class "Default")
      (node (ref "L2") (pin "1") (pinfunction "1_1") (pintype "bidirectional"))
      (node (ref "U1") (pin "7") (pinfunction "SW_7") (pintype "bidirectional"))
    )
    (net (code "53") (name "unconnected-(IC1-NC_1-Pad12)") (class "Default")
      (node (ref "IC1") (pin "12") (pinfunction "NC_1_12") (pintype "bidirectional"))
    )
    (net (code "54") (name "unconnected-(IC1-NC_2-Pad20)") (class "Default")
      (node (ref "IC1") (pin "20") (pinfunction "NC_2_20") (pintype "bidirectional"))
    )
    (net (code "55") (name "unconnected-(IC3-NC_1-Pad8)") (class "Default")
      (node (ref "IC3") (pin "8") (pinfunction "NC_1_8") (pintype "bidirectional"))
    )
    (net (code "56") (name "unconnected-(J1-Pad23)") (class "Default")
      (node (ref "J1") (pin "23") (pinfunction "23_23") (pintype "bidirectional"))
    )
    (net (code "57") (name "unconnected-(J1-Pad25)") (class "Default")
      (node (ref "J1") (pin "25") (pinfunction "25_25") (pintype "bidirectional"))
    )
    (net (code "58") (name "unconnected-(J1-Pad29)") (class "Default")
      (node (ref "J1") (pin "29") (pinfunction "29_29") (pintype "bidirectional"))
    )
    (net (code "59") (name "unconnected-(J1-Pad30)") (class "Default")
      (node (ref "J1") (pin "30") (pinfunction "30_30") (pintype "bidirectional"))
    )
    (net (code "60") (name "unconnected-(J1-Pad31)") (class "Default")
      (node (ref "J1") (pin "31") (pinfunction "31_31") (pintype "bidirectional"))
    )
    (net (code "61") (name "unconnected-(J1-Pad32)") (class "Default")
      (node (ref "J1") (pin "32") (pinfunction "32_32") (pintype "bidirectional"))
    )
    (net (code "62") (name "unconnected-(J1-Pad35)") (class "Default")
      (node (ref "J1") (pin "35") (pinfunction "35_35") (pintype "bidirectional"))
    )
    (net (code "63") (name "unconnected-(J1-Pad36)") (class "Default")
      (node (ref "J1") (pin "36") (pinfunction "36_36") (pintype "bidirectional"))
    )
    (net (code "64") (name "unconnected-(J1-Pad37)") (class "Default")
      (node (ref "J1") (pin "37") (pinfunction "37_37") (pintype "bidirectional"))
    )
    (net (code "65") (name "unconnected-(J1-Pad38)") (class "Default")
      (node (ref "J1") (pin "38") (pinfunction "38_38") (pintype "bidirectional"))
    )
    (net (code "66") (name "unconnected-(J2-Pad17)") (class "Default")
      (node (ref "J2") (pin "17") (pinfunction "17_17") (pintype "bidirectional"))
    )
    (net (code "67") (name "unconnected-(J2-Pad18)") (class "Default")
      (node (ref "J2") (pin "18") (pinfunction "18_18") (pintype "bidirectional"))
    )
    (net (code "68") (name "unconnected-(U1-PG-Pad6)") (class "Default")
      (node (ref "U1") (pin "6") (pinfunction "PG_6") (pintype "bidirectional"))
    )
  )
)
